# the_staff.net
KiCad netlist of a schematic drawn in EAGLE
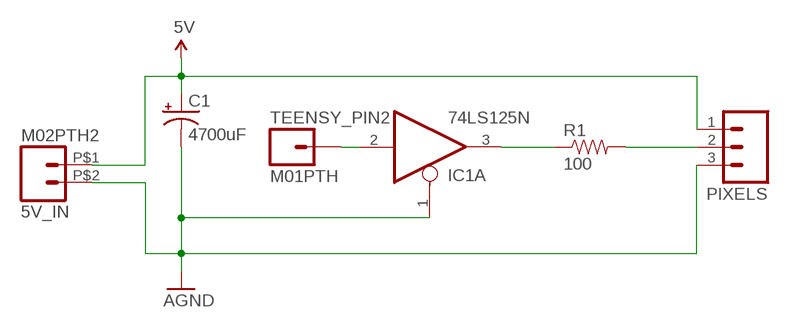
[diagram p0: schematic, sheet 1]

(export (version "E")
  (design (tool "Eeschema 10.0.6"))
  (components
    (comp (ref "5V_IN")
      (value "M02PTH2")
      (footprint "eagle-import:1X02_BIG")
      (libsource (lib "eagle-import") (part "M02PTH2"))
    )
    (comp (ref "C1")
      (value "4700uF")
      (footprint "eagle-import:CPOL-RADIAL-1000UF-63V")
      (libsource (lib "eagle-import") (part "CAP_POLPTH3"))
    )
    (comp (ref "IC1")
      (value "74LS125N")
      (footprint "eagle-import:DIL14")
      (libsource (lib "eagle-import") (part "74125NLS"))
    )
    (comp (ref "PIXELS")
      (value "M03JST-PTH")
      (footprint "eagle-import:JST-3-PTH")
      (libsource (lib "eagle-import") (part "M03JST-PTH"))
    )
    (comp (ref "R1")
      (value "100")
      (footprint "eagle-import:AXIAL-0.4")
      (libsource (lib "eagle-import") (part "RESISTORPTH-1/4W"))
    )
    (comp (ref "TEENSY_PIN2")
      (value "M01PTH")
      (footprint "eagle-import:1X01")
      (libsource (lib "eagle-import") (part "M01PTH"))
    )
  )
  (nets
    (net (code "1") (name "5V") (class "Default")
      (node (ref "5V_IN") (pin "P$1") (pinfunction "1_P$1") (pintype "passive"))
      (node (ref "C1") (pin "1") (pinfunction "+_1") (pintype "passive"))
      (node (ref "PIXELS") (pin "1") (pinfunction "1_1") (pintype "passive"))
    )
    (net (code "2") (name "AGND") (class "Default")
      (node (ref "5V_IN") (pin "P$2") (pinfunction "2_P$2") (pintype "passive"))
      (node (ref "C1") (pin "2") (pinfunction "-_2") (pintype "passive"))
      (node (ref "IC1") (pin "1") (pinfunction "OE_1") (pintype "input"))
      (node (ref "PIXELS") (pin "3") (pinfunction "3_3") (pintype "passive"))
    )
    (net (code "3") (name "Net-(IC1A-I)") (class "Default")
      (node (ref "IC1") (pin "2") (pinfunction "I_2") (pintype "input"))
      (node (ref "TEENSY_PIN2") (pin "1") (pinfunction "1_1") (pintype "passive"))
    )
    (net (code "4") (name "Net-(IC1A-O)") (class "Default")
      (node (ref "IC1") (pin "3") (pinfunction "O_3") (pintype "tri_state"))
      (node (ref "R1") (pin "P$1") (pinfunction "1_P$1") (pintype "passive"))
    )
    (net (code "5") (name "Net-(R1-2)") (class "Default")
      (node (ref "PIXELS") (pin "2") (pinfunction "2_2") (pintype "passive"))
      (node (ref "R1") (pin "P$2") (pinfunction "2_P$2") (pintype "passive"))
    )
  )
)
